# PSU3.net
KiCad netlist of a schematic drawn in EAGLE
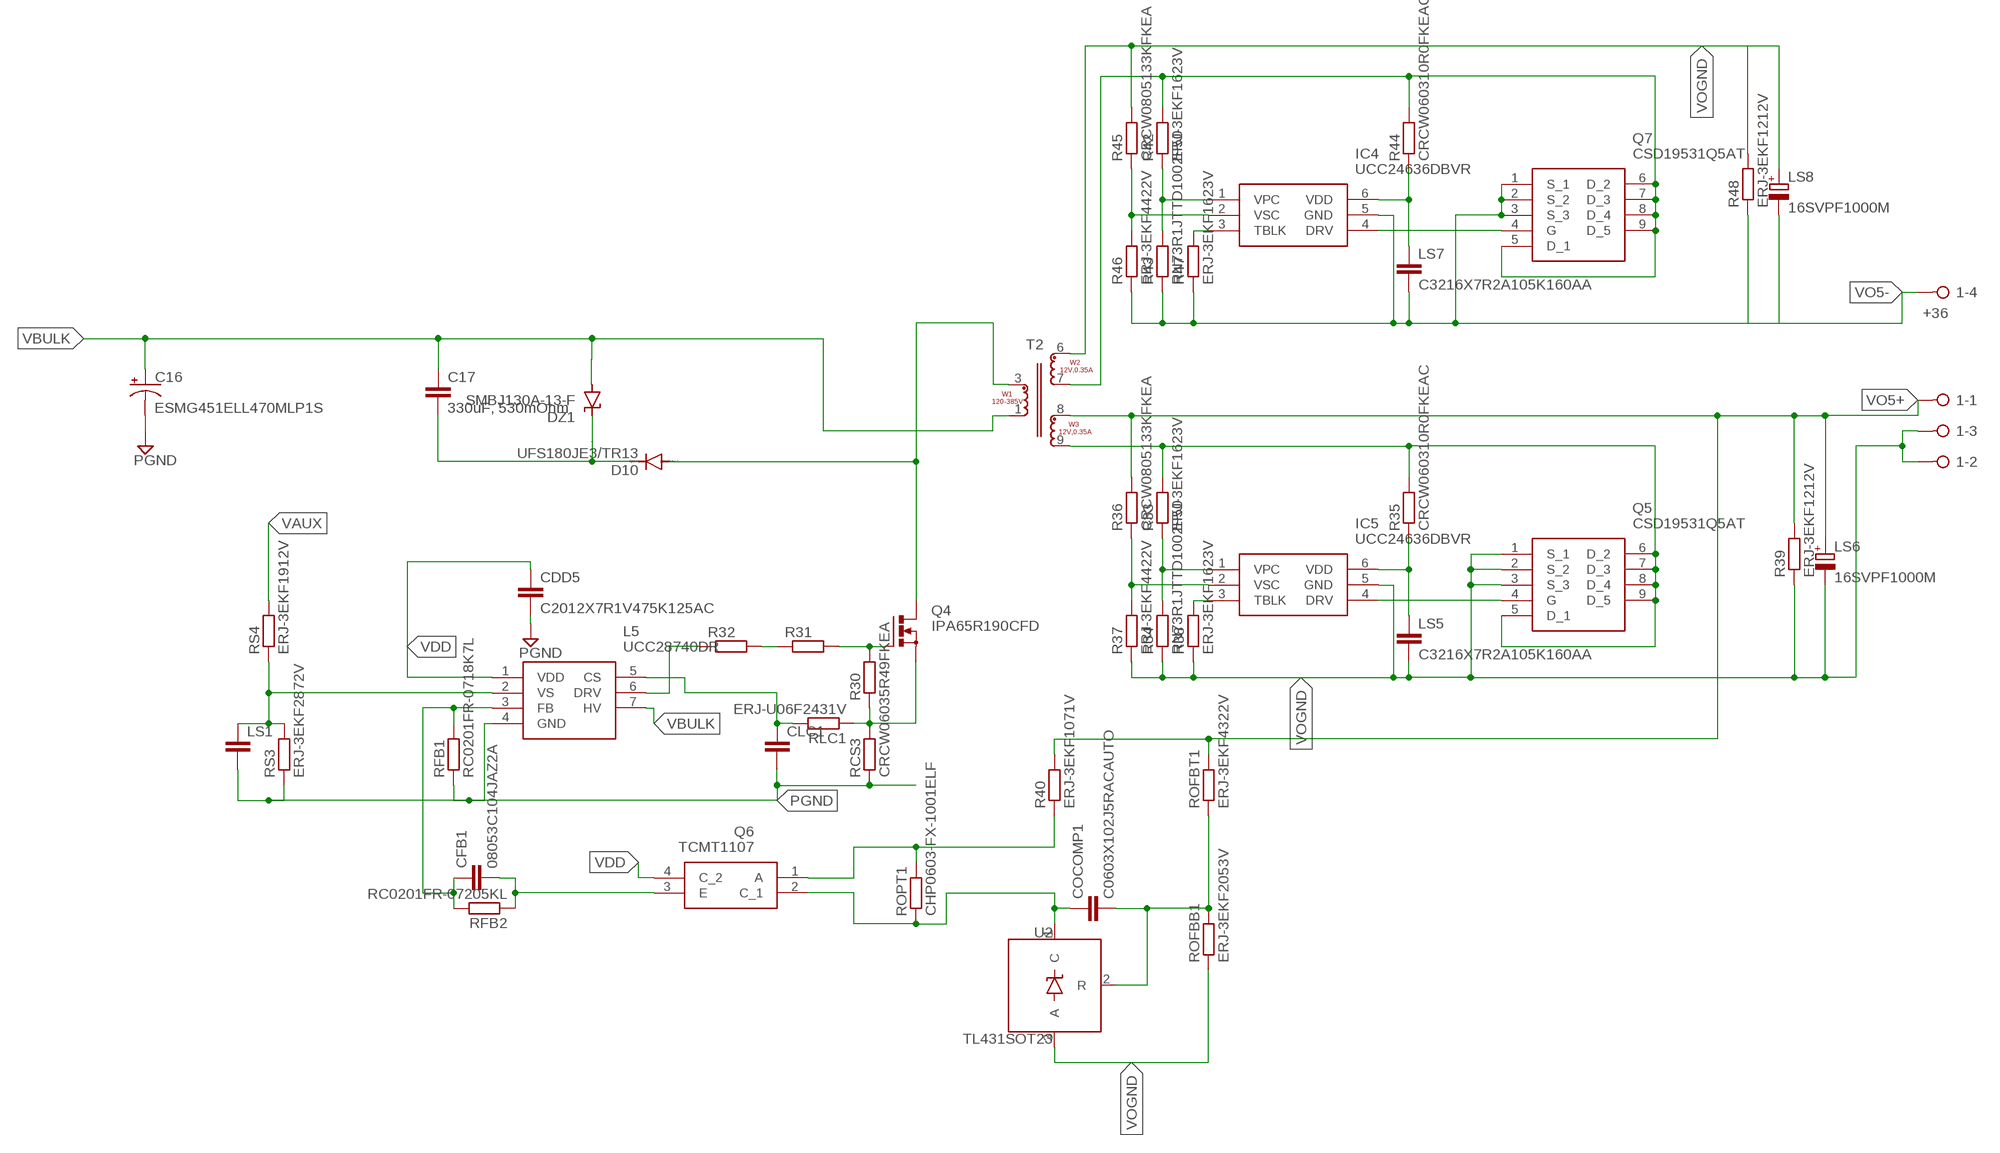
[diagram p0: schematic, sheet 1]

(export (version "E")
  (design (tool "Eeschema 10.0.6"))
  (components
    (comp (ref "1")
      (value "+36")
      (footprint "eagle-import:W237-4P")
      (libsource (lib "eagle-import") (part "W237-04P"))
    )
    (comp (ref "C16")
      (value "ESMG451ELL470MLP1S")
      (footprint "eagle-import:E7,5-16")
      (libsource (lib "eagle-import") (part "CPOL-USE7.5-16"))
    )
    (comp (ref "C17")
      (value "330uF, 530mOhm")
      (footprint "eagle-import:C0805")
      (libsource (lib "eagle-import") (part "C-EUC0805"))
    )
    (comp (ref "CDD5")
      (value "C2012X7R1V475K125AC")
      (footprint "eagle-import:C0805")
      (libsource (lib "eagle-import") (part "C-EUC0805"))
    )
    (comp (ref "CFB1")
      (value "08053C104JAZ2A")
      (footprint "eagle-import:C0805")
      (libsource (lib "eagle-import") (part "C-EUC0805"))
    )
    (comp (ref "CLC1")
      (value "C-EUC0603")
      (footprint "eagle-import:C0603")
      (libsource (lib "eagle-import") (part "C-EUC0603"))
    )
    (comp (ref "COCOMP1")
      (value "C0603X102J5RACAUTO")
      (footprint "eagle-import:C0603")
      (libsource (lib "eagle-import") (part "C-EUC0603"))
    )
    (comp (ref "D10")
      (value "UFS180JE3/TR13")
      (footprint "eagle-import:DO214BA")
      (libsource (lib "eagle-import") (part "DIODE-DO214BA"))
    )
    (comp (ref "DZ1")
      (value "SMBJ130A-13-F")
      (footprint "eagle-import:SMBJ")
      (libsource (lib "eagle-import") (part "SUPPRESSOR-SMBJ"))
    )
    (comp (ref "IC4")
      (value "UCC24636DBVR")
      (footprint "eagle-import:SOT95P280X145-6N")
      (fields (field (name "MOUSER_PART_NUMBER") "595-UCC24636DBVR"))
      (libsource (lib "eagle-import") (part "UCC24636DBVR"))
    )
    (comp (ref "IC5")
      (value "UCC24636DBVR")
      (footprint "eagle-import:SOT95P280X145-6N")
      (fields (field (name "MOUSER_PART_NUMBER") "595-UCC24636DBVR"))
      (libsource (lib "eagle-import") (part "UCC24636DBVR"))
    )
    (comp (ref "L5")
      (value "UCC28740DR")
      (footprint "eagle-import:D(R-PDSO-G7)")
      (fields (field (name "MOUSER_PART_NUMBER") "595-UCC28740DR"))
      (libsource (lib "eagle-import") (part "UCC28740DR"))
    )
    (comp (ref "LS1")
      (value "C-EUC0805")
      (footprint "eagle-import:C0805")
      (libsource (lib "eagle-import") (part "C-EUC0805"))
    )
    (comp (ref "LS5")
      (value "C3216X7R2A105K160AA")
      (footprint "eagle-import:C1206")
      (libsource (lib "eagle-import") (part "C-EUC1206"))
    )
    (comp (ref "LS6")
      (value "16SVPF1000M")
      (footprint "eagle-import:153CLV-0810")
      (libsource (lib "eagle-import") (part "CPOL-EU153CLV-0810"))
    )
    (comp (ref "LS7")
      (value "C3216X7R2A105K160AA")
      (footprint "eagle-import:C1206")
      (libsource (lib "eagle-import") (part "C-EUC1206"))
    )
    (comp (ref "LS8")
      (value "16SVPF1000M")
      (footprint "eagle-import:153CLV-0810")
      (libsource (lib "eagle-import") (part "CPOL-EU153CLV-0810"))
    )
    (comp (ref "Q4")
      (value "IPA65R190CFD")
      (footprint "eagle-import:TO220BV")
      (libsource (lib "eagle-import") (part "PMOSFET_NTO220BV"))
    )
    (comp (ref "Q5")
      (value "CSD19531Q5AT")
      (footprint "eagle-import:CSD19531Q5AT")
      (fields
        (field (name "MOUSER_PART_NUMBER") "595-CSD19531Q5AT")
        (field (name "RS_PART_NUMBER") "8239259P")
      )
      (libsource (lib "eagle-import") (part "CSD19531Q5AT"))
    )
    (comp (ref "Q6")
      (value "TCMT1107")
      (footprint "eagle-import:SOIC127P700X230-4N")
      (fields (field (name "MOUSER_PART_NUMBER") "782-TCMT1107") (field (name "RS_PART_NUMBER") "6998341P"))
      (libsource (lib "eagle-import") (part "TCMT1107"))
    )
    (comp (ref "Q7")
      (value "CSD19531Q5AT")
      (footprint "eagle-import:CSD19531Q5AT")
      (fields
        (field (name "MOUSER_PART_NUMBER") "595-CSD19531Q5AT")
        (field (name "RS_PART_NUMBER") "8239259P")
      )
      (libsource (lib "eagle-import") (part "CSD19531Q5AT"))
    )
    (comp (ref "R30")
      (value "R-EU_R0805")
      (footprint "eagle-import:R0805")
      (libsource (lib "eagle-import") (part "R-EU_R0805"))
    )
    (comp (ref "R31")
      (value "R-EU_R0805")
      (footprint "eagle-import:R0805")
      (libsource (lib "eagle-import") (part "R-EU_R0805"))
    )
    (comp (ref "R32")
      (value "R-EU_R0805")
      (footprint "eagle-import:R0805")
      (libsource (lib "eagle-import") (part "R-EU_R0805"))
    )
    (comp (ref "R33")
      (value "ERJ-3EKF1623V")
      (footprint "eagle-import:R0603")
      (libsource (lib "eagle-import") (part "R-EU_R0603"))
    )
    (comp (ref "R34")
      (value "RN73R1JTTD1002F50")
      (footprint "eagle-import:R0603")
      (libsource (lib "eagle-import") (part "R-EU_R0603"))
    )
    (comp (ref "R35")
      (value "CRCW060310R0FKEAC")
      (footprint "eagle-import:R0805")
      (libsource (lib "eagle-import") (part "R-EU_R0805"))
    )
    (comp (ref "R36")
      (value "CRCW0805133KFKEA")
      (footprint "eagle-import:R0805")
      (libsource (lib "eagle-import") (part "R-EU_R0805"))
    )
    (comp (ref "R37")
      (value "ERJ-3EKF4422V")
      (footprint "eagle-import:R0603")
      (libsource (lib "eagle-import") (part "R-EU_R0603"))
    )
    (comp (ref "R38")
      (value "ERJ-3EKF1623V")
      (footprint "eagle-import:R0603")
      (libsource (lib "eagle-import") (part "R-EU_R0603"))
    )
    (comp (ref "R39")
      (value "ERJ-3EKF1212V")
      (footprint "eagle-import:R0603")
      (libsource (lib "eagle-import") (part "R-EU_R0603"))
    )
    (comp (ref "R40")
      (value "ERJ-3EKF1071V")
      (footprint "eagle-import:R0603")
      (libsource (lib "eagle-import") (part "R-EU_R0603"))
    )
    (comp (ref "R42")
      (value "ERJ-3EKF1623V")
      (footprint "eagle-import:R0603")
      (libsource (lib "eagle-import") (part "R-EU_R0603"))
    )
    (comp (ref "R43")
      (value "RN73R1JTTD1002F50")
      (footprint "eagle-import:R0603")
      (libsource (lib "eagle-import") (part "R-EU_R0603"))
    )
    (comp (ref "R44")
      (value "CRCW060310R0FKEAC")
      (footprint "eagle-import:R0805")
      (libsource (lib "eagle-import") (part "R-EU_R0805"))
    )
    (comp (ref "R45")
      (value "CRCW0805133KFKEA")
      (footprint "eagle-import:R0805")
      (libsource (lib "eagle-import") (part "R-EU_R0805"))
    )
    (comp (ref "R46")
      (value "ERJ-3EKF4422V")
      (footprint "eagle-import:R0603")
      (libsource (lib "eagle-import") (part "R-EU_R0603"))
    )
    (comp (ref "R47")
      (value "ERJ-3EKF1623V")
      (footprint "eagle-import:R0603")
      (libsource (lib "eagle-import") (part "R-EU_R0603"))
    )
    (comp (ref "R48")
      (value "ERJ-3EKF1212V")
      (footprint "eagle-import:R0603")
      (libsource (lib "eagle-import") (part "R-EU_R0603"))
    )
    (comp (ref "RCS3")
      (value "CRCW06035R49FKEA")
      (footprint "eagle-import:R0603")
      (libsource (lib "eagle-import") (part "R-EU_R0603"))
    )
    (comp (ref "RFB1")
      (value "RC0201FR-0718K7L")
      (footprint "eagle-import:R0201")
      (libsource (lib "eagle-import") (part "R-EU_R0201"))
    )
    (comp (ref "RFB2")
      (value "RC0201FR-07205KL")
      (footprint "eagle-import:R0201")
      (libsource (lib "eagle-import") (part "R-EU_R0201"))
    )
    (comp (ref "RLC1")
      (value "ERJ-U06F2431V")
      (footprint "eagle-import:R0805")
      (libsource (lib "eagle-import") (part "R-EU_R0805"))
    )
    (comp (ref "ROFBB1")
      (value "ERJ-3EKF2053V")
      (footprint "eagle-import:R0603")
      (libsource (lib "eagle-import") (part "R-EU_R0603"))
    )
    (comp (ref "ROFBT1")
      (value "ERJ-3EKF4322V")
      (footprint "eagle-import:R0603")
      (libsource (lib "eagle-import") (part "R-EU_R0603"))
    )
    (comp (ref "ROPT1")
      (value "CHP0603-FX-1001ELF")
      (footprint "eagle-import:R0603")
      (libsource (lib "eagle-import") (part "R-EU_R0603"))
    )
    (comp (ref "RS3")
      (value "ERJ-3EKF2872V")
      (footprint "eagle-import:R0603")
      (libsource (lib "eagle-import") (part "R-EU_R0603"))
    )
    (comp (ref "RS4")
      (value "ERJ-3EKF1912V")
      (footprint "eagle-import:R0603")
      (libsource (lib "eagle-import") (part "R-EU_R0603"))
    )
    (comp (ref "T2")
      (value "WE-UNIT_7491182112_749118215")
      (footprint "eagle-import:WE-UNIT_E16_8_5")
      (libsource (lib "eagle-import") (part "WE-UNIT_7491182112_749118215"))
    )
    (comp (ref "U2")
      (value "TL431SOT23")
      (footprint "eagle-import:SOT23-3")
      (libsource (lib "eagle-import") (part "TL431SOT23"))
    )
  )
  (nets
    (net (code "1") (name "Net-(C17-Pad2)") (class "Default")
      (node (ref "C17") (pin "2") (pinfunction "2_2") (pintype "passive"))
      (node (ref "D10") (pin "C") (pinfunction "C_C") (pintype "passive"))
      (node (ref "DZ1") (pin "C") (pinfunction "C_C") (pintype "passive"))
    )
    (net (code "2") (name "Net-(IC4-DRV)") (class "Default")
      (node (ref "IC4") (pin "4") (pinfunction "DRV_4") (pintype "bidirectional"))
      (node (ref "Q7") (pin "4") (pinfunction "G_4") (pintype "bidirectional"))
    )
    (net (code "3") (name "Net-(IC4-TBLK)") (class "Default")
      (node (ref "IC4") (pin "3") (pinfunction "TBLK_3") (pintype "bidirectional"))
      (node (ref "R47") (pin "2") (pinfunction "2_2") (pintype "passive"))
    )
    (net (code "4") (name "Net-(IC4-VDD)") (class "Default")
      (node (ref "IC4") (pin "6") (pinfunction "VDD_6") (pintype "bidirectional"))
      (node (ref "LS7") (pin "1") (pinfunction "1_1") (pintype "passive"))
      (node (ref "R44") (pin "1") (pinfunction "1_1") (pintype "passive"))
    )
    (net (code "5") (name "Net-(IC4-VPC)") (class "Default")
      (node (ref "IC4") (pin "1") (pinfunction "VPC_1") (pintype "bidirectional"))
      (node (ref "R42") (pin "1") (pinfunction "1_1") (pintype "passive"))
      (node (ref "R43") (pin "2") (pinfunction "2_2") (pintype "passive"))
    )
    (net (code "6") (name "Net-(IC4-VSC)") (class "Default")
      (node (ref "IC4") (pin "2") (pinfunction "VSC_2") (pintype "bidirectional"))
      (node (ref "R45") (pin "1") (pinfunction "1_1") (pintype "passive"))
      (node (ref "R46") (pin "2") (pinfunction "2_2") (pintype "passive"))
    )
    (net (code "7") (name "Net-(IC5-DRV)") (class "Default")
      (node (ref "IC5") (pin "4") (pinfunction "DRV_4") (pintype "bidirectional"))
      (node (ref "Q5") (pin "4") (pinfunction "G_4") (pintype "bidirectional"))
    )
    (net (code "8") (name "Net-(IC5-TBLK)") (class "Default")
      (node (ref "IC5") (pin "3") (pinfunction "TBLK_3") (pintype "bidirectional"))
      (node (ref "R38") (pin "2") (pinfunction "2_2") (pintype "passive"))
    )
    (net (code "9") (name "Net-(IC5-VDD)") (class "Default")
      (node (ref "IC5") (pin "6") (pinfunction "VDD_6") (pintype "bidirectional"))
      (node (ref "LS5") (pin "1") (pinfunction "1_1") (pintype "passive"))
      (node (ref "R35") (pin "1") (pinfunction "1_1") (pintype "passive"))
    )
    (net (code "10") (name "Net-(IC5-VPC)") (class "Default")
      (node (ref "IC5") (pin "1") (pinfunction "VPC_1") (pintype "bidirectional"))
      (node (ref "R33") (pin "1") (pinfunction "1_1") (pintype "passive"))
      (node (ref "R34") (pin "2") (pinfunction "2_2") (pintype "passive"))
    )
    (net (code "11") (name "Net-(IC5-VSC)") (class "Default")
      (node (ref "IC5") (pin "2") (pinfunction "VSC_2") (pintype "bidirectional"))
      (node (ref "R36") (pin "1") (pinfunction "1_1") (pintype "passive"))
      (node (ref "R37") (pin "2") (pinfunction "2_2") (pintype "passive"))
    )
    (net (code "12") (name "Net-(L5-CS)") (class "Default")
      (node (ref "CLC1") (pin "1") (pinfunction "1_1") (pintype "passive"))
      (node (ref "L5") (pin "5") (pinfunction "CS_5") (pintype "bidirectional"))
      (node (ref "RLC1") (pin "2") (pinfunction "2_2") (pintype "passive"))
    )
    (net (code "13") (name "Net-(L5-DRV)") (class "Default")
      (node (ref "L5") (pin "6") (pinfunction "DRV_6") (pintype "bidirectional"))
      (node (ref "R32") (pin "1") (pinfunction "1_1") (pintype "passive"))
    )
    (net (code "14") (name "Net-(L5-FB)") (class "Default")
      (node (ref "CFB1") (pin "1") (pinfunction "1_1") (pintype "passive"))
      (node (ref "L5") (pin "3") (pinfunction "FB_3") (pintype "bidirectional"))
      (node (ref "RFB1") (pin "2") (pinfunction "2_2") (pintype "passive"))
      (node (ref "RFB2") (pin "2") (pinfunction "2_2") (pintype "passive"))
    )
    (net (code "15") (name "Net-(L5-VS)") (class "Default")
      (node (ref "L5") (pin "2") (pinfunction "VS_2") (pintype "bidirectional"))
      (node (ref "LS1") (pin "1") (pinfunction "1_1") (pintype "passive"))
      (node (ref "RS3") (pin "2") (pinfunction "2_2") (pintype "passive"))
      (node (ref "RS4") (pin "1") (pinfunction "1_1") (pintype "passive"))
    )
    (net (code "16") (name "Net-(Q4-PadG)") (class "Default")
      (node (ref "Q4") (pin "G") (pinfunction "G_G") (pintype "passive"))
      (node (ref "R30") (pin "2") (pinfunction "2_2") (pintype "passive"))
      (node (ref "R31") (pin "2") (pinfunction "2_2") (pintype "passive"))
    )
    (net (code "17") (name "Net-(Q4-PadS)") (class "Default")
      (node (ref "Q4") (pin "S") (pinfunction "S_S") (pintype "passive"))
      (node (ref "R30") (pin "1") (pinfunction "1_1") (pintype "passive"))
      (node (ref "RCS3") (pin "2") (pinfunction "2_2") (pintype "passive"))
      (node (ref "RLC1") (pin "1") (pinfunction "1_1") (pintype "passive"))
    )
    (net (code "18") (name "Net-(Q5-D_1)") (class "Default")
      (node (ref "Q5") (pin "5") (pinfunction "D_1_5") (pintype "bidirectional"))
      (node (ref "Q5") (pin "6") (pinfunction "D_2_6") (pintype "bidirectional"))
      (node (ref "Q5") (pin "7") (pinfunction "D_3_7") (pintype "bidirectional"))
      (node (ref "Q5") (pin "8") (pinfunction "D_4_8") (pintype "bidirectional"))
      (node (ref "Q5") (pin "9") (pinfunction "D_5_9") (pintype "bidirectional"))
      (node (ref "R33") (pin "2") (pinfunction "2_2") (pintype "passive"))
      (node (ref "R35") (pin "2") (pinfunction "2_2") (pintype "passive"))
      (node (ref "T2") (pin "9") (pinfunction "5_9") (pintype "passive"))
    )
    (net (code "19") (name "Net-(Q6-A)") (class "Default")
      (node (ref "Q6") (pin "1") (pinfunction "A_1") (pintype "bidirectional"))
      (node (ref "R40") (pin "1") (pinfunction "1_1") (pintype "passive"))
      (node (ref "ROPT1") (pin "2") (pinfunction "2_2") (pintype "passive"))
    )
    (net (code "20") (name "Net-(Q6-C_1)") (class "Default")
      (node (ref "COCOMP1") (pin "1") (pinfunction "1_1") (pintype "passive"))
      (node (ref "Q6") (pin "2") (pinfunction "C_1_2") (pintype "bidirectional"))
      (node (ref "ROPT1") (pin "1") (pinfunction "1_1") (pintype "passive"))
      (node (ref "U2") (pin "1") (pinfunction "C_1") (pintype "bidirectional"))
    )
    (net (code "21") (name "Net-(Q6-E)") (class "Default")
      (node (ref "CFB1") (pin "2") (pinfunction "2_2") (pintype "passive"))
      (node (ref "Q6") (pin "3") (pinfunction "E_3") (pintype "bidirectional"))
      (node (ref "RFB2") (pin "1") (pinfunction "1_1") (pintype "passive"))
    )
    (net (code "22") (name "Net-(Q7-D_1)") (class "Default")
      (node (ref "Q7") (pin "5") (pinfunction "D_1_5") (pintype "bidirectional"))
      (node (ref "Q7") (pin "6") (pinfunction "D_2_6") (pintype "bidirectional"))
      (node (ref "Q7") (pin "7") (pinfunction "D_3_7") (pintype "bidirectional"))
      (node (ref "Q7") (pin "8") (pinfunction "D_4_8") (pintype "bidirectional"))
      (node (ref "Q7") (pin "9") (pinfunction "D_5_9") (pintype "bidirectional"))
      (node (ref "R42") (pin "2") (pinfunction "2_2") (pintype "passive"))
      (node (ref "R44") (pin "2") (pinfunction "2_2") (pintype "passive"))
      (node (ref "T2") (pin "7") (pinfunction "3_7") (pintype "passive"))
    )
    (net (code "23") (name "Net-(R31-Pad1)") (class "Default")
      (node (ref "R31") (pin "1") (pinfunction "1_1") (pintype "passive"))
      (node (ref "R32") (pin "2") (pinfunction "2_2") (pintype "passive"))
    )
    (net (code "24") (name "Net-(T2-1)") (class "Default")
      (node (ref "D10") (pin "A") (pinfunction "A_A") (pintype "passive"))
      (node (ref "Q4") (pin "D") (pinfunction "D_D") (pintype "passive"))
      (node (ref "T2") (pin "3") (pinfunction "1_3") (pintype "passive"))
    )
    (net (code "25") (name "Net-(U2-R)") (class "Default")
      (node (ref "COCOMP1") (pin "2") (pinfunction "2_2") (pintype "passive"))
      (node (ref "ROFBB1") (pin "2") (pinfunction "2_2") (pintype "passive"))
      (node (ref "ROFBT1") (pin "1") (pinfunction "1_1") (pintype "passive"))
      (node (ref "U2") (pin "2") (pinfunction "R_2") (pintype "bidirectional"))
    )
    (net (code "26") (name "PGND") (class "Default")
      (node (ref "C16") (pin "-") (pinfunction "-_-") (pintype "passive"))
      (node (ref "CDD5") (pin "2") (pinfunction "2_2") (pintype "passive"))
      (node (ref "CLC1") (pin "2") (pinfunction "2_2") (pintype "passive"))
      (node (ref "L5") (pin "4") (pinfunction "GND_4") (pintype "bidirectional"))
      (node (ref "LS1") (pin "2") (pinfunction "2_2") (pintype "passive"))
      (node (ref "RCS3") (pin "1") (pinfunction "1_1") (pintype "passive"))
      (node (ref "RFB1") (pin "1") (pinfunction "1_1") (pintype "passive"))
      (node (ref "RS3") (pin "1") (pinfunction "1_1") (pintype "passive"))
    )
    (net (code "27") (name "VAUX") (class "Default")
      (node (ref "RS4") (pin "2") (pinfunction "2_2") (pintype "passive"))
    )
    (net (code "28") (name "VBULK") (class "Default")
      (node (ref "C16") (pin "+") (pinfunction "+_+") (pintype "passive"))
      (node (ref "C17") (pin "1") (pinfunction "1_1") (pintype "passive"))
      (node (ref "DZ1") (pin "A") (pinfunction "A_A") (pintype "passive"))
      (node (ref "L5") (pin "7") (pinfunction "HV_7") (pintype "bidirectional"))
      (node (ref "T2") (pin "1") (pinfunction "6_1") (pintype "passive"))
    )
    (net (code "29") (name "VDD") (class "Default")
      (node (ref "CDD5") (pin "1") (pinfunction "1_1") (pintype "passive"))
      (node (ref "L5") (pin "1") (pinfunction "VDD_1") (pintype "bidirectional"))
      (node (ref "Q6") (pin "4") (pinfunction "C_2_4") (pintype "bidirectional"))
    )
    (net (code "30") (name "VO5+") (class "Default")
      (node (ref "1") (pin "1") (pinfunction "KL_1") (pintype "passive"))
      (node (ref "LS6") (pin "+") (pinfunction "+_+") (pintype "passive"))
      (node (ref "R36") (pin "2") (pinfunction "2_2") (pintype "passive"))
      (node (ref "R39") (pin "2") (pinfunction "2_2") (pintype "passive"))
      (node (ref "R40") (pin "2") (pinfunction "2_2") (pintype "passive"))
      (node (ref "ROFBT1") (pin "2") (pinfunction "2_2") (pintype "passive"))
      (node (ref "T2") (pin "8") (pinfunction "4_8") (pintype "passive"))
    )
    (net (code "31") (name "VO5-") (class "Default")
      (node (ref "1") (pin "4") (pinfunction "KL_4") (pintype "passive"))
      (node (ref "IC4") (pin "5") (pinfunction "GND_5") (pintype "bidirectional"))
      (node (ref "LS7") (pin "2") (pinfunction "2_2") (pintype "passive"))
      (node (ref "LS8") (pin "-") (pinfunction "-_-") (pintype "passive"))
      (node (ref "Q7") (pin "1") (pinfunction "S_1_1") (pintype "bidirectional"))
      (node (ref "Q7") (pin "2") (pinfunction "S_2_2") (pintype "bidirectional"))
      (node (ref "Q7") (pin "3") (pinfunction "S_3_3") (pintype "bidirectional"))
      (node (ref "R43") (pin "1") (pinfunction "1_1") (pintype "passive"))
      (node (ref "R46") (pin "1") (pinfunction "1_1") (pintype "passive"))
      (node (ref "R47") (pin "1") (pinfunction "1_1") (pintype "passive"))
      (node (ref "R48") (pin "1") (pinfunction "1_1") (pintype "passive"))
    )
    (net (code "32") (name "VOGND") (class "Default")
      (node (ref "1") (pin "2") (pinfunction "KL_2") (pintype "passive"))
      (node (ref "1") (pin "3") (pinfunction "KL_3") (pintype "passive"))
      (node (ref "IC5") (pin "5") (pinfunction "GND_5") (pintype "bidirectional"))
      (node (ref "LS5") (pin "2") (pinfunction "2_2") (pintype "passive"))
      (node (ref "LS6") (pin "-") (pinfunction "-_-") (pintype "passive"))
      (node (ref "LS8") (pin "+") (pinfunction "+_+") (pintype "passive"))
      (node (ref "Q5") (pin "1") (pinfunction "S_1_1") (pintype "bidirectional"))
      (node (ref "Q5") (pin "2") (pinfunction "S_2_2") (pintype "bidirectional"))
      (node (ref "Q5") (pin "3") (pinfunction "S_3_3") (pintype "bidirectional"))
      (node (ref "R34") (pin "1") (pinfunction "1_1") (pintype "passive"))
      (node (ref "R37") (pin "1") (pinfunction "1_1") (pintype "passive"))
      (node (ref "R38") (pin "1") (pinfunction "1_1") (pintype "passive"))
      (node (ref "R39") (pin "1") (pinfunction "1_1") (pintype "passive"))
      (node (ref "R45") (pin "2") (pinfunction "2_2") (pintype "passive"))
      (node (ref "R48") (pin "2") (pinfunction "2_2") (pintype "passive"))
      (node (ref "ROFBB1") (pin "1") (pinfunction "1_1") (pintype "passive"))
      (node (ref "T2") (pin "6") (pinfunction "2_6") (pintype "passive"))
      (node (ref "U2") (pin "3") (pinfunction "A_3") (pintype "bidirectional"))
    )
  )
)
